# LED4BUS0805_v01.net
KiCad netlist of a schematic drawn in EAGLE
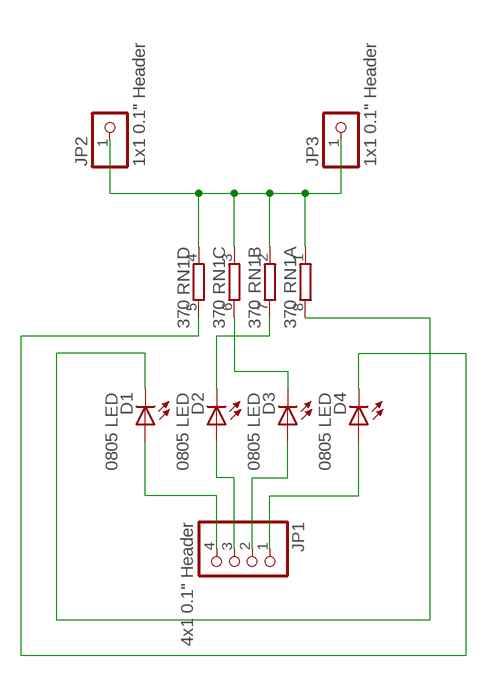
[diagram p0: schematic, sheet 1]

(export (version "E")
  (design (tool "Eeschema 10.0.6"))
  (components
    (comp (ref "D1")
      (value "0805 LED")
      (footprint "eagle-import:CHIP-LED0805")
      (libsource (lib "eagle-import") (part "LEDCHIP-LED0805"))
    )
    (comp (ref "D2")
      (value "0805 LED")
      (footprint "eagle-import:CHIP-LED0805")
      (libsource (lib "eagle-import") (part "LEDCHIP-LED0805"))
    )
    (comp (ref "D3")
      (value "0805 LED")
      (footprint "eagle-import:CHIP-LED0805")
      (libsource (lib "eagle-import") (part "LEDCHIP-LED0805"))
    )
    (comp (ref "D4")
      (value "0805 LED")
      (footprint "eagle-import:CHIP-LED0805")
      (libsource (lib "eagle-import") (part "LEDCHIP-LED0805"))
    )
    (comp (ref "JP1")
      (value "4x1 0.1\" Header")
      (footprint "eagle-import:1X04")
      (libsource (lib "eagle-import") (part "PINHD-1X4"))
    )
    (comp (ref "JP2")
      (value "1x1 0.1\" Header")
      (footprint "eagle-import:1X01")
      (libsource (lib "eagle-import") (part "PINHD-1X1"))
    )
    (comp (ref "JP3")
      (value "1x1 0.1\" Header")
      (footprint "eagle-import:1X01")
      (libsource (lib "eagle-import") (part "PINHD-1X1"))
    )
    (comp (ref "RN1")
      (value "370")
      (footprint "eagle-import:0603-ARV")
      (libsource (lib "eagle-import") (part "4R-N0603-ARV"))
    )
  )
  (nets
    (net (code "1") (name "Net-(D1-PadA)") (class "Default")
      (node (ref "D1") (pin "A") (pinfunction "A_A") (pintype "passive"))
      (node (ref "JP1") (pin "4") (pinfunction "4_4") (pintype "passive"))
    )
    (net (code "2") (name "Net-(D2-PadA)") (class "Default")
      (node (ref "D2") (pin "A") (pinfunction "A_A") (pintype "passive"))
      (node (ref "JP1") (pin "3") (pinfunction "3_3") (pintype "passive"))
    )
    (net (code "3") (name "Net-(D3-PadA)") (class "Default")
      (node (ref "D3") (pin "A") (pinfunction "A_A") (pintype "passive"))
      (node (ref "JP1") (pin "2") (pinfunction "2_2") (pintype "passive"))
    )
    (net (code "4") (name "Net-(D4-PadA)") (class "Default")
      (node (ref "D4") (pin "A") (pinfunction "A_A") (pintype "passive"))
      (node (ref "JP1") (pin "1") (pinfunction "1_1") (pintype "passive"))
    )
    (net (code "5") (name "Net-(RN1A-2)") (class "Default")
      (node (ref "D1") (pin "C") (pinfunction "C_C") (pintype "passive"))
      (node (ref "RN1") (pin "8") (pinfunction "2_8") (pintype "passive"))
    )
    (net (code "6") (name "Net-(RN1B-1)") (class "Default")
      (node (ref "JP2") (pin "1") (pinfunction "1_1") (pintype "passive"))
      (node (ref "JP3") (pin "1") (pinfunction "1_1") (pintype "passive"))
      (node (ref "RN1") (pin "1") (pinfunction "1_1") (pintype "passive"))
      (node (ref "RN1") (pin "2") (pinfunction "1_2") (pintype "passive"))
      (node (ref "RN1") (pin "3") (pinfunction "1_3") (pintype "passive"))
      (node (ref "RN1") (pin "4") (pinfunction "1_4") (pintype "passive"))
    )
    (net (code "7") (name "Net-(RN1B-2)") (class "Default")
      (node (ref "D2") (pin "C") (pinfunction "C_C") (pintype "passive"))
      (node (ref "RN1") (pin "7") (pinfunction "2_7") (pintype "passive"))
    )
    (net (code "8") (name "Net-(RN1C-2)") (class "Default")
      (node (ref "D3") (pin "C") (pinfunction "C_C") (pintype "passive"))
      (node (ref "RN1") (pin "6") (pinfunction "2_6") (pintype "passive"))
    )
    (net (code "9") (name "Net-(RN1D-2)") (class "Default")
      (node (ref "D4") (pin "C") (pinfunction "C_C") (pintype "passive"))
      (node (ref "RN1") (pin "5") (pinfunction "2_5") (pintype "passive"))
    )
  )
)
